# AUX_Power.net
KiCad netlist of a schematic drawn in Altium Designer
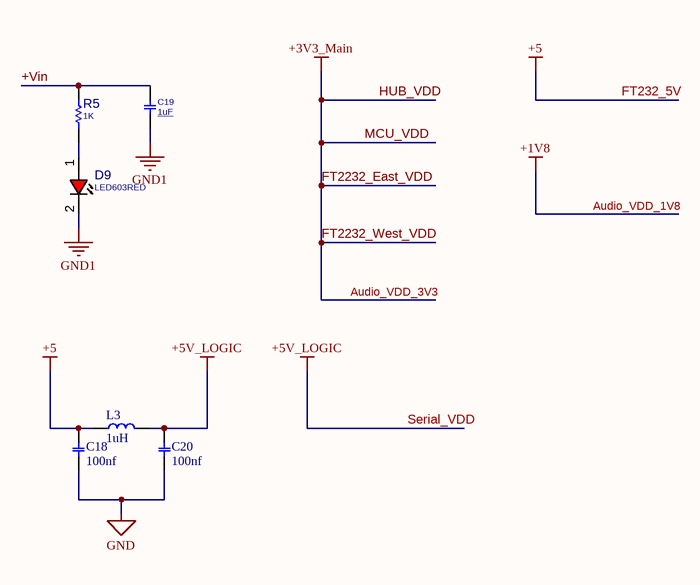
[diagram p0: AUX Power.SchDoc]

(export (version "E")
  (design (tool "Eeschema 10.0.6"))
  (components
    (comp (ref "C18")
      (value "100nf")
      (footprint "C1206")
      (description "Capacitor C SMD 1206")
      (libsource (lib "Capacitor") (part "Capacitor C SMD 1206"))
    )
    (comp (ref "C19")
      (value "1uF")
      (footprint "0603")
      (description "CAP, FILM, 1uF, 16V, Acryl, 20%, 1210")
      (fields (field (name "MANF_P#") "ECP-U1C105MA5") (field (name "MANF") "Panasonic"))
      (libsource (lib "cap_film_smd_passive") (part "CAP_SMD_FILM_1u16v_1210"))
    )
    (comp (ref "C20")
      (value "100nf")
      (footprint "C1206")
      (description "Capacitor C SMD 1206")
      (libsource (lib "Capacitor") (part "Capacitor C SMD 1206"))
    )
    (comp (ref "D9")
      (value "LED603RED")
      (footprint "LED0603RED")
      (description "LED, SMD, 0603, RED")
      (fields (field (name "MANF") "MANF") (field (name "MANF_P#") "MANF_PART#"))
      (libsource (lib "led(diode)") (part "LED_SMD_0603_RED"))
    )
    (comp (ref "L3")
      (value "1uH")
      (footprint "L1812")
      (description "Inductor SMD NC 1812")
      (libsource (lib "Inductor") (part "Inductor SMD NC 1812"))
    )
    (comp (ref "R5")
      (value "1K")
      (footprint "R0603")
      (description "RESISTOR, SMD")
      (libsource (lib "passive_smd") (part "RES_SMD_0603"))
    )
  )
  (nets
    (net (code "3") (name "+5") (class "Default")
      (node (ref "C18") (pin "2") (pinfunction "2_2") (pintype "passive"))
      (node (ref "L3") (pin "1") (pinfunction "1_1") (pintype "passive"))
    )
    (net (code "4") (name "+5V_LOGIC") (class "Default")
      (node (ref "C20") (pin "2") (pinfunction "2_2") (pintype "passive"))
      (node (ref "L3") (pin "2") (pinfunction "2_2") (pintype "passive"))
    )
    (net (code "5") (name "/+Vin") (class "Default")
      (node (ref "C19") (pin "1") (pinfunction "1_1") (pintype "passive"))
      (node (ref "R5") (pin "2") (pinfunction "2_2") (pintype "passive"))
    )
    (net (code "6") (name "GND") (class "Default")
      (node (ref "C18") (pin "1") (pinfunction "1_1") (pintype "passive"))
      (node (ref "C20") (pin "1") (pinfunction "1_1") (pintype "passive"))
    )
    (net (code "7") (name "GND1") (class "Default")
      (node (ref "C19") (pin "2") (pinfunction "2_2") (pintype "passive"))
      (node (ref "D9") (pin "2") (pinfunction "CATHODE_2") (pintype "passive"))
    )
    (net (code "8") (name "Net-(D9-ANODE)") (class "Default")
      (node (ref "D9") (pin "1") (pinfunction "ANODE_1") (pintype "passive"))
      (node (ref "R5") (pin "1") (pinfunction "1_1") (pintype "passive"))
    )
  )
)
